# stm32f4discovery-daugherboard.net
KiCad netlist of a schematic drawn in EAGLE
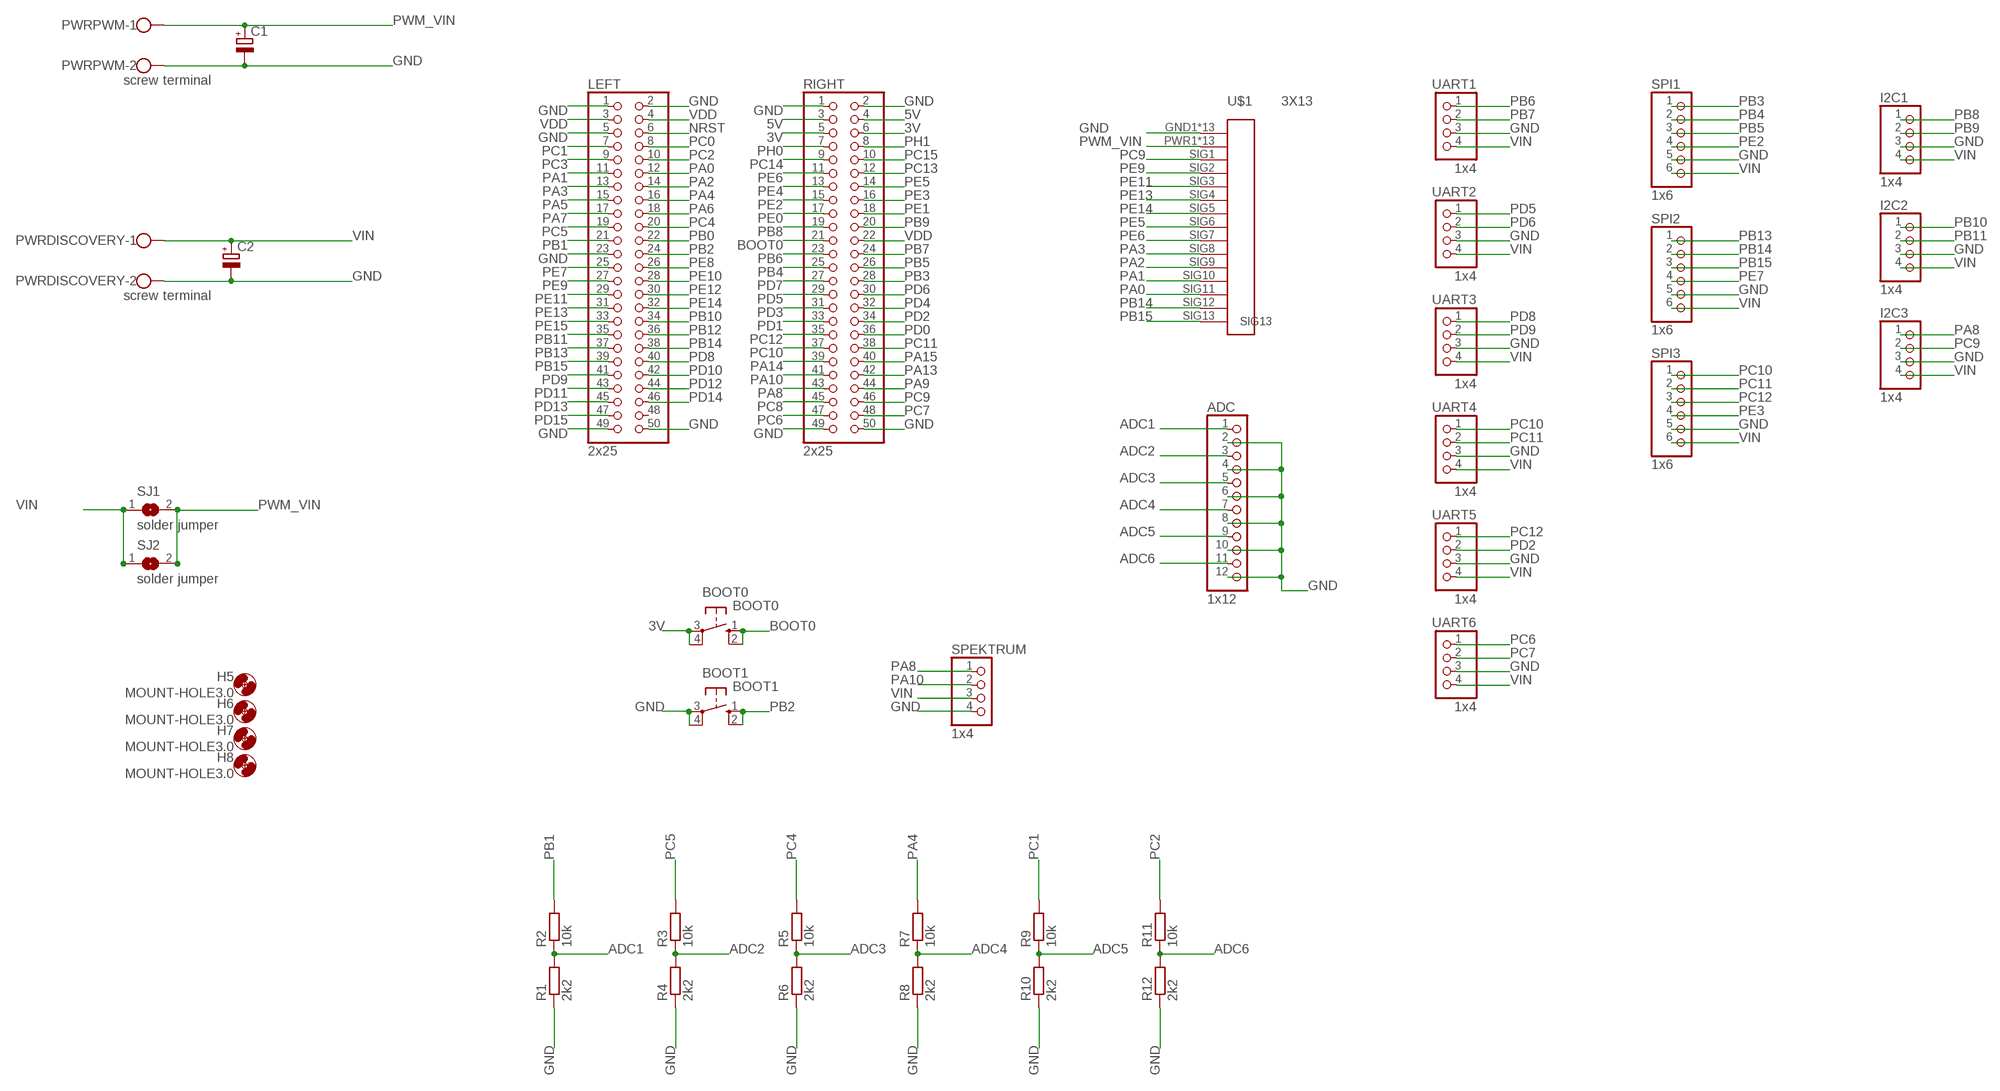
[diagram p0: schematic, sheet 1]

(export (version "E")
  (design (tool "Eeschema 10.0.6"))
  (components
    (comp (ref "ADC")
      (value "1x12")
      (footprint "eagle-import:1X12_90")
      (libsource (lib "eagle-import") (part "PINHD-1X12/90"))
    )
    (comp (ref "BOOT0")
      (value "BOOT0")
      (footprint "eagle-import:B3F-10XX")
      (fields (field (name "MPN") "B3F-1000"))
      (libsource (lib "eagle-import") (part "10-XX"))
    )
    (comp (ref "BOOT1")
      (value "BOOT1")
      (footprint "eagle-import:B3F-10XX")
      (fields (field (name "MPN") "B3F-1000"))
      (libsource (lib "eagle-import") (part "10-XX"))
    )
    (comp (ref "C1")
      (value "CPOL-EU153CLV-0807")
      (footprint "eagle-import:153CLV-0807")
      (libsource (lib "eagle-import") (part "CPOL-EU153CLV-0807"))
    )
    (comp (ref "C2")
      (value "CPOL-EU153CLV-0807")
      (footprint "eagle-import:153CLV-0807")
      (libsource (lib "eagle-import") (part "CPOL-EU153CLV-0807"))
    )
    (comp (ref "H5")
      (value "MOUNT-HOLE3.0")
      (footprint "eagle-import:3,0")
      (libsource (lib "eagle-import") (part "MOUNT-HOLE3.0"))
    )
    (comp (ref "H6")
      (value "MOUNT-HOLE3.0")
      (footprint "eagle-import:3,0")
      (libsource (lib "eagle-import") (part "MOUNT-HOLE3.0"))
    )
    (comp (ref "H7")
      (value "MOUNT-HOLE3.0")
      (footprint "eagle-import:3,0")
      (libsource (lib "eagle-import") (part "MOUNT-HOLE3.0"))
    )
    (comp (ref "H8")
      (value "MOUNT-HOLE3.0")
      (footprint "eagle-import:3,0")
      (libsource (lib "eagle-import") (part "MOUNT-HOLE3.0"))
    )
    (comp (ref "I2C1")
      (value "1x4")
      (footprint "eagle-import:1X04_90")
      (libsource (lib "eagle-import") (part "PINHD-1X4/90"))
    )
    (comp (ref "I2C2")
      (value "1x4")
      (footprint "eagle-import:1X04_90")
      (libsource (lib "eagle-import") (part "PINHD-1X4/90"))
    )
    (comp (ref "I2C3")
      (value "1x4")
      (footprint "eagle-import:1X04_90")
      (libsource (lib "eagle-import") (part "PINHD-1X4/90"))
    )
    (comp (ref "LEFT")
      (value "2x25")
      (footprint "eagle-import:2X25")
      (libsource (lib "eagle-import") (part "PINHD-2X25"))
    )
    (comp (ref "PWRDISCOVERY")
      (value "screw terminal")
      (footprint "eagle-import:W237-102")
      (fields (field (name "MPN") "237-102"))
      (libsource (lib "eagle-import") (part "W237-102"))
    )
    (comp (ref "PWRPWM")
      (value "screw terminal")
      (footprint "eagle-import:W237-102")
      (fields (field (name "MPN") "237-102"))
      (libsource (lib "eagle-import") (part "W237-102"))
    )
    (comp (ref "R1")
      (value "2k2")
      (footprint "eagle-import:M0805")
      (libsource (lib "eagle-import") (part "R-EU_M0805"))
    )
    (comp (ref "R2")
      (value "10k")
      (footprint "eagle-import:M0805")
      (libsource (lib "eagle-import") (part "R-EU_M0805"))
    )
    (comp (ref "R3")
      (value "10k")
      (footprint "eagle-import:M0805")
      (libsource (lib "eagle-import") (part "R-EU_M0805"))
    )
    (comp (ref "R4")
      (value "2k2")
      (footprint "eagle-import:M0805")
      (libsource (lib "eagle-import") (part "R-EU_M0805"))
    )
    (comp (ref "R5")
      (value "10k")
      (footprint "eagle-import:M0805")
      (libsource (lib "eagle-import") (part "R-EU_M0805"))
    )
    (comp (ref "R6")
      (value "2k2")
      (footprint "eagle-import:M0805")
      (libsource (lib "eagle-import") (part "R-EU_M0805"))
    )
    (comp (ref "R7")
      (value "10k")
      (footprint "eagle-import:M0805")
      (libsource (lib "eagle-import") (part "R-EU_M0805"))
    )
    (comp (ref "R8")
      (value "2k2")
      (footprint "eagle-import:M0805")
      (libsource (lib "eagle-import") (part "R-EU_M0805"))
    )
    (comp (ref "R9")
      (value "10k")
      (footprint "eagle-import:M0805")
      (libsource (lib "eagle-import") (part "R-EU_M0805"))
    )
    (comp (ref "R10")
      (value "2k2")
      (footprint "eagle-import:M0805")
      (libsource (lib "eagle-import") (part "R-EU_M0805"))
    )
    (comp (ref "R11")
      (value "10k")
      (footprint "eagle-import:M0805")
      (libsource (lib "eagle-import") (part "R-EU_M0805"))
    )
    (comp (ref "R12")
      (value "2k2")
      (footprint "eagle-import:M0805")
      (libsource (lib "eagle-import") (part "R-EU_M0805"))
    )
    (comp (ref "RIGHT")
      (value "2x25")
      (footprint "eagle-import:2X25")
      (libsource (lib "eagle-import") (part "PINHD-2X25"))
    )
    (comp (ref "SJ1")
      (value "solder jumper")
      (footprint "eagle-import:SJW")
      (libsource (lib "eagle-import") (part "SJW"))
    )
    (comp (ref "SJ2")
      (value "solder jumper")
      (footprint "eagle-import:SJW")
      (libsource (lib "eagle-import") (part "SJW"))
    )
    (comp (ref "SPEKTRUM")
      (value "1x4")
      (footprint "eagle-import:1X04_90")
      (libsource (lib "eagle-import") (part "PINHD-1X4/90"))
    )
    (comp (ref "SPI1")
      (value "1x6")
      (footprint "eagle-import:1X06_90")
      (libsource (lib "eagle-import") (part "PINHD-1X6/90"))
    )
    (comp (ref "SPI2")
      (value "1x6")
      (footprint "eagle-import:1X06_90")
      (libsource (lib "eagle-import") (part "PINHD-1X6/90"))
    )
    (comp (ref "SPI3")
      (value "1x6")
      (footprint "eagle-import:1X06_90")
      (libsource (lib "eagle-import") (part "PINHD-1X6/90"))
    )
    (comp (ref "U$1")
      (value "3X13")
      (footprint "eagle-import:3X13")
      (libsource (lib "eagle-import") (part "3X13"))
    )
    (comp (ref "UART1")
      (value "1x4")
      (footprint "eagle-import:1X04_90")
      (libsource (lib "eagle-import") (part "PINHD-1X4/90"))
    )
    (comp (ref "UART2")
      (value "1x4")
      (footprint "eagle-import:1X04_90")
      (libsource (lib "eagle-import") (part "PINHD-1X4/90"))
    )
    (comp (ref "UART3")
      (value "1x4")
      (footprint "eagle-import:1X04_90")
      (libsource (lib "eagle-import") (part "PINHD-1X4/90"))
    )
    (comp (ref "UART4")
      (value "1x4")
      (footprint "eagle-import:1X04_90")
      (libsource (lib "eagle-import") (part "PINHD-1X4/90"))
    )
    (comp (ref "UART5")
      (value "1x4")
      (footprint "eagle-import:1X04_90")
      (libsource (lib "eagle-import") (part "PINHD-1X4/90"))
    )
    (comp (ref "UART6")
      (value "1x4")
      (footprint "eagle-import:1X04_90")
      (libsource (lib "eagle-import") (part "PINHD-1X4/90"))
    )
  )
  (nets
    (net (code "1") (name "/3V") (class "Default")
      (node (ref "BOOT0") (pin "3") (pinfunction "P_3") (pintype "passive"))
      (node (ref "BOOT0") (pin "4") (pinfunction "P1_4") (pintype "passive"))
      (node (ref "RIGHT") (pin "5") (pinfunction "5_5") (pintype "passive"))
      (node (ref "RIGHT") (pin "6") (pinfunction "6_6") (pintype "passive"))
    )
    (net (code "2") (name "/5V") (class "Default")
      (node (ref "RIGHT") (pin "3") (pinfunction "3_3") (pintype "passive"))
      (node (ref "RIGHT") (pin "4") (pinfunction "4_4") (pintype "passive"))
    )
    (net (code "3") (name "/ADC1") (class "Default")
      (node (ref "ADC") (pin "1") (pinfunction "1_1") (pintype "passive"))
      (node (ref "R1") (pin "2") (pinfunction "2_2") (pintype "passive"))
      (node (ref "R2") (pin "1") (pinfunction "1_1") (pintype "passive"))
    )
    (net (code "4") (name "/ADC2") (class "Default")
      (node (ref "ADC") (pin "3") (pinfunction "3_3") (pintype "passive"))
      (node (ref "R3") (pin "1") (pinfunction "1_1") (pintype "passive"))
      (node (ref "R4") (pin "2") (pinfunction "2_2") (pintype "passive"))
    )
    (net (code "5") (name "/ADC3") (class "Default")
      (node (ref "ADC") (pin "5") (pinfunction "5_5") (pintype "passive"))
      (node (ref "R5") (pin "1") (pinfunction "1_1") (pintype "passive"))
      (node (ref "R6") (pin "2") (pinfunction "2_2") (pintype "passive"))
    )
    (net (code "6") (name "/ADC4") (class "Default")
      (node (ref "ADC") (pin "7") (pinfunction "7_7") (pintype "passive"))
      (node (ref "R7") (pin "1") (pinfunction "1_1") (pintype "passive"))
      (node (ref "R8") (pin "2") (pinfunction "2_2") (pintype "passive"))
    )
    (net (code "7") (name "/ADC5") (class "Default")
      (node (ref "ADC") (pin "9") (pinfunction "9_9") (pintype "passive"))
      (node (ref "R10") (pin "2") (pinfunction "2_2") (pintype "passive"))
      (node (ref "R9") (pin "1") (pinfunction "1_1") (pintype "passive"))
    )
    (net (code "8") (name "/ADC6") (class "Default")
      (node (ref "ADC") (pin "11") (pinfunction "11_11") (pintype "passive"))
      (node (ref "R11") (pin "1") (pinfunction "1_1") (pintype "passive"))
      (node (ref "R12") (pin "2") (pinfunction "2_2") (pintype "passive"))
    )
    (net (code "9") (name "/BOOT0") (class "Default")
      (node (ref "BOOT0") (pin "1") (pinfunction "S_1") (pintype "passive"))
      (node (ref "BOOT0") (pin "2") (pinfunction "S1_2") (pintype "passive"))
      (node (ref "RIGHT") (pin "21") (pinfunction "21_21") (pintype "passive"))
    )
    (net (code "10") (name "/GND") (class "Default")
      (node (ref "ADC") (pin "10") (pinfunction "10_10") (pintype "passive"))
      (node (ref "ADC") (pin "12") (pinfunction "12_12") (pintype "passive"))
      (node (ref "ADC") (pin "2") (pinfunction "2_2") (pintype "passive"))
      (node (ref "ADC") (pin "4") (pinfunction "4_4") (pintype "passive"))
      (node (ref "ADC") (pin "6") (pinfunction "6_6") (pintype "passive"))
      (node (ref "ADC") (pin "8") (pinfunction "8_8") (pintype "passive"))
      (node (ref "BOOT1") (pin "3") (pinfunction "P_3") (pintype "passive"))
      (node (ref "BOOT1") (pin "4") (pinfunction "P1_4") (pintype "passive"))
      (node (ref "C1") (pin "-") (pinfunction "-_-") (pintype "passive"))
      (node (ref "C2") (pin "-") (pinfunction "-_-") (pintype "passive"))
      (node (ref "I2C1") (pin "3") (pinfunction "3_3") (pintype "passive"))
      (node (ref "I2C2") (pin "3") (pinfunction "3_3") (pintype "passive"))
      (node (ref "I2C3") (pin "3") (pinfunction "3_3") (pintype "passive"))
      (node (ref "LEFT") (pin "1") (pinfunction "1_1") (pintype "passive"))
      (node (ref "LEFT") (pin "2") (pinfunction "2_2") (pintype "passive"))
      (node (ref "LEFT") (pin "23") (pinfunction "23_23") (pintype "passive"))
      (node (ref "LEFT") (pin "49") (pinfunction "49_49") (pintype "passive"))
      (node (ref "LEFT") (pin "5") (pinfunction "5_5") (pintype "passive"))
      (node (ref "LEFT") (pin "50") (pinfunction "50_50") (pintype "passive"))
      (node (ref "PWRDISCOVERY") (pin "2") (pinfunction "KL_2") (pintype "passive"))
      (node (ref "PWRPWM") (pin "2") (pinfunction "KL_2") (pintype "passive"))
      (node (ref "R1") (pin "1") (pinfunction "1_1") (pintype "passive"))
      (node (ref "R10") (pin "1") (pinfunction "1_1") (pintype "passive"))
      (node (ref "R12") (pin "1") (pinfunction "1_1") (pintype "passive"))
      (node (ref "R4") (pin "1") (pinfunction "1_1") (pintype "passive"))
      (node (ref "R6") (pin "1") (pinfunction "1_1") (pintype "passive"))
      (node (ref "R8") (pin "1") (pinfunction "1_1") (pintype "passive"))
      (node (ref "RIGHT") (pin "1") (pinfunction "1_1") (pintype "passive"))
      (node (ref "RIGHT") (pin "2") (pinfunction "2_2") (pintype "passive"))
      (node (ref "RIGHT") (pin "49") (pinfunction "49_49") (pintype "passive"))
      (node (ref "RIGHT") (pin "50") (pinfunction "50_50") (pintype "passive"))
      (node (ref "SPEKTRUM") (pin "4") (pinfunction "4_4") (pintype "passive"))
      (node (ref "SPI1") (pin "5") (pinfunction "5_5") (pintype "passive"))
      (node (ref "SPI2") (pin "5") (pinfunction "5_5") (pintype "passive"))
      (node (ref "SPI3") (pin "5") (pinfunction "5_5") (pintype "passive"))
      (node (ref "U$1") (pin "GND1") (pinfunction "GND_GND1") (pintype "bidirectional"))
      (node (ref "U$1") (pin "GND10") (pinfunction "GND_GND10") (pintype "bidirectional"))
      (node (ref "U$1") (pin "GND11") (pinfunction "GND_GND11") (pintype "bidirectional"))
      (node (ref "U$1") (pin "GND12") (pinfunction "GND_GND12") (pintype "bidirectional"))
      (node (ref "U$1") (pin "GND13") (pinfunction "GND_GND13") (pintype "bidirectional"))
      (node (ref "U$1") (pin "GND2") (pinfunction "GND_GND2") (pintype "bidirectional"))
      (node (ref "U$1") (pin "GND3") (pinfunction "GND_GND3") (pintype "bidirectional"))
      (node (ref "U$1") (pin "GND4") (pinfunction "GND_GND4") (pintype "bidirectional"))
      (node (ref "U$1") (pin "GND5") (pinfunction "GND_GND5") (pintype "bidirectional"))
      (node (ref "U$1") (pin "GND6") (pinfunction "GND_GND6") (pintype "bidirectional"))
      (node (ref "U$1") (pin "GND7") (pinfunction "GND_GND7") (pintype "bidirectional"))
      (node (ref "U$1") (pin "GND8") (pinfunction "GND_GND8") (pintype "bidirectional"))
      (node (ref "U$1") (pin "GND9") (pinfunction "GND_GND9") (pintype "bidirectional"))
      (node (ref "UART1") (pin "3") (pinfunction "3_3") (pintype "passive"))
      (node (ref "UART2") (pin "3") (pinfunction "3_3") (pintype "passive"))
      (node (ref "UART3") (pin "3") (pinfunction "3_3") (pintype "passive"))
      (node (ref "UART4") (pin "3") (pinfunction "3_3") (pintype "passive"))
      (node (ref "UART5") (pin "3") (pinfunction "3_3") (pintype "passive"))
      (node (ref "UART6") (pin "3") (pinfunction "3_3") (pintype "passive"))
    )
    (net (code "11") (name "/NRST") (class "Default")
      (node (ref "LEFT") (pin "6") (pinfunction "6_6") (pintype "passive"))
    )
    (net (code "12") (name "/PA0") (class "Default")
      (node (ref "LEFT") (pin "12") (pinfunction "12_12") (pintype "passive"))
      (node (ref "U$1") (pin "SIG11") (pinfunction "SIG11_SIG11") (pintype "bidirectional"))
    )
    (net (code "13") (name "/PA1") (class "Default")
      (node (ref "LEFT") (pin "11") (pinfunction "11_11") (pintype "passive"))
      (node (ref "U$1") (pin "SIG10") (pinfunction "SIG10_SIG10") (pintype "bidirectional"))
    )
    (net (code "14") (name "/PA2") (class "Default")
      (node (ref "LEFT") (pin "14") (pinfunction "14_14") (pintype "passive"))
      (node (ref "U$1") (pin "SIG9") (pinfunction "SIG9_SIG9") (pintype "bidirectional"))
    )
    (net (code "15") (name "/PA3") (class "Default")
      (node (ref "LEFT") (pin "13") (pinfunction "13_13") (pintype "passive"))
      (node (ref "U$1") (pin "SIG8") (pinfunction "SIG8_SIG8") (pintype "bidirectional"))
    )
    (net (code "16") (name "/PA4") (class "Default")
      (node (ref "LEFT") (pin "16") (pinfunction "16_16") (pintype "passive"))
      (node (ref "R7") (pin "2") (pinfunction "2_2") (pintype "passive"))
    )
    (net (code "17") (name "/PA5") (class "Default")
      (node (ref "LEFT") (pin "15") (pinfunction "15_15") (pintype "passive"))
    )
    (net (code "18") (name "/PA6") (class "Default")
      (node (ref "LEFT") (pin "18") (pinfunction "18_18") (pintype "passive"))
    )
    (net (code "19") (name "/PA7") (class "Default")
      (node (ref "LEFT") (pin "17") (pinfunction "17_17") (pintype "passive"))
    )
    (net (code "20") (name "/PA8") (class "Default")
      (node (ref "I2C3") (pin "1") (pinfunction "1_1") (pintype "passive"))
      (node (ref "RIGHT") (pin "43") (pinfunction "43_43") (pintype "passive"))
      (node (ref "SPEKTRUM") (pin "1") (pinfunction "1_1") (pintype "passive"))
    )
    (net (code "21") (name "/PA9") (class "Default")
      (node (ref "RIGHT") (pin "44") (pinfunction "44_44") (pintype "passive"))
    )
    (net (code "22") (name "/PA10") (class "Default")
      (node (ref "RIGHT") (pin "41") (pinfunction "41_41") (pintype "passive"))
      (node (ref "SPEKTRUM") (pin "2") (pinfunction "2_2") (pintype "passive"))
    )
    (net (code "23") (name "/PA13") (class "Default")
      (node (ref "RIGHT") (pin "42") (pinfunction "42_42") (pintype "passive"))
    )
    (net (code "24") (name "/PA14") (class "Default")
      (node (ref "RIGHT") (pin "39") (pinfunction "39_39") (pintype "passive"))
    )
    (net (code "25") (name "/PA15") (class "Default")
      (node (ref "RIGHT") (pin "40") (pinfunction "40_40") (pintype "passive"))
    )
    (net (code "26") (name "/PB0") (class "Default")
      (node (ref "LEFT") (pin "22") (pinfunction "22_22") (pintype "passive"))
    )
    (net (code "27") (name "/PB1") (class "Default")
      (node (ref "LEFT") (pin "21") (pinfunction "21_21") (pintype "passive"))
      (node (ref "R2") (pin "2") (pinfunction "2_2") (pintype "passive"))
    )
    (net (code "28") (name "/PB2") (class "Default")
      (node (ref "BOOT1") (pin "1") (pinfunction "S_1") (pintype "passive"))
      (node (ref "BOOT1") (pin "2") (pinfunction "S1_2") (pintype "passive"))
      (node (ref "LEFT") (pin "24") (pinfunction "24_24") (pintype "passive"))
    )
    (net (code "29") (name "/PB3") (class "Default")
      (node (ref "RIGHT") (pin "28") (pinfunction "28_28") (pintype "passive"))
      (node (ref "SPI1") (pin "1") (pinfunction "1_1") (pintype "passive"))
    )
    (net (code "30") (name "/PB4") (class "Default")
      (node (ref "RIGHT") (pin "25") (pinfunction "25_25") (pintype "passive"))
      (node (ref "SPI1") (pin "2") (pinfunction "2_2") (pintype "passive"))
    )
    (net (code "31") (name "/PB5") (class "Default")
      (node (ref "RIGHT") (pin "26") (pinfunction "26_26") (pintype "passive"))
      (node (ref "SPI1") (pin "3") (pinfunction "3_3") (pintype "passive"))
    )
    (net (code "32") (name "/PB6") (class "Default")
      (node (ref "RIGHT") (pin "23") (pinfunction "23_23") (pintype "passive"))
      (node (ref "UART1") (pin "1") (pinfunction "1_1") (pintype "passive"))
    )
    (net (code "33") (name "/PB7") (class "Default")
      (node (ref "RIGHT") (pin "24") (pinfunction "24_24") (pintype "passive"))
      (node (ref "UART1") (pin "2") (pinfunction "2_2") (pintype "passive"))
    )
    (net (code "34") (name "/PB8") (class "Default")
      (node (ref "I2C1") (pin "1") (pinfunction "1_1") (pintype "passive"))
      (node (ref "RIGHT") (pin "19") (pinfunction "19_19") (pintype "passive"))
    )
    (net (code "35") (name "/PB9") (class "Default")
      (node (ref "I2C1") (pin "2") (pinfunction "2_2") (pintype "passive"))
      (node (ref "RIGHT") (pin "20") (pinfunction "20_20") (pintype "passive"))
    )
    (net (code "36") (name "/PB10") (class "Default")
      (node (ref "I2C2") (pin "1") (pinfunction "1_1") (pintype "passive"))
      (node (ref "LEFT") (pin "34") (pinfunction "34_34") (pintype "passive"))
    )
    (net (code "37") (name "/PB11") (class "Default")
      (node (ref "I2C2") (pin "2") (pinfunction "2_2") (pintype "passive"))
      (node (ref "LEFT") (pin "35") (pinfunction "35_35") (pintype "passive"))
    )
    (net (code "38") (name "/PB12") (class "Default")
      (node (ref "LEFT") (pin "36") (pinfunction "36_36") (pintype "passive"))
    )
    (net (code "39") (name "/PB13") (class "Default")
      (node (ref "LEFT") (pin "37") (pinfunction "37_37") (pintype "passive"))
      (node (ref "SPI2") (pin "1") (pinfunction "1_1") (pintype "passive"))
    )
    (net (code "40") (name "/PB14") (class "Default")
      (node (ref "LEFT") (pin "38") (pinfunction "38_38") (pintype "passive"))
      (node (ref "SPI2") (pin "2") (pinfunction "2_2") (pintype "passive"))
      (node (ref "U$1") (pin "SIG12") (pinfunction "SIG12_SIG12") (pintype "bidirectional"))
    )
    (net (code "41") (name "/PB15") (class "Default")
      (node (ref "LEFT") (pin "39") (pinfunction "39_39") (pintype "passive"))
      (node (ref "SPI2") (pin "3") (pinfunction "3_3") (pintype "passive"))
      (node (ref "U$1") (pin "SIG13") (pinfunction "SIG13_SIG13") (pintype "bidirectional"))
    )
    (net (code "42") (name "/PC0") (class "Default")
      (node (ref "LEFT") (pin "8") (pinfunction "8_8") (pintype "passive"))
    )
    (net (code "43") (name "/PC1") (class "Default")
      (node (ref "LEFT") (pin "7") (pinfunction "7_7") (pintype "passive"))
      (node (ref "R9") (pin "2") (pinfunction "2_2") (pintype "passive"))
    )
    (net (code "44") (name "/PC2") (class "Default")
      (node (ref "LEFT") (pin "10") (pinfunction "10_10") (pintype "passive"))
      (node (ref "R11") (pin "2") (pinfunction "2_2") (pintype "passive"))
    )
    (net (code "45") (name "/PC3") (class "Default")
      (node (ref "LEFT") (pin "9") (pinfunction "9_9") (pintype "passive"))
    )
    (net (code "46") (name "/PC4") (class "Default")
      (node (ref "LEFT") (pin "20") (pinfunction "20_20") (pintype "passive"))
      (node (ref "R5") (pin "2") (pinfunction "2_2") (pintype "passive"))
    )
    (net (code "47") (name "/PC5") (class "Default")
      (node (ref "LEFT") (pin "19") (pinfunction "19_19") (pintype "passive"))
      (node (ref "R3") (pin "2") (pinfunction "2_2") (pintype "passive"))
    )
    (net (code "48") (name "/PC6") (class "Default")
      (node (ref "RIGHT") (pin "47") (pinfunction "47_47") (pintype "passive"))
      (node (ref "UART6") (pin "1") (pinfunction "1_1") (pintype "passive"))
    )
    (net (code "49") (name "/PC7") (class "Default")
      (node (ref "RIGHT") (pin "48") (pinfunction "48_48") (pintype "passive"))
      (node (ref "UART6") (pin "2") (pinfunction "2_2") (pintype "passive"))
    )
    (net (code "50") (name "/PC8") (class "Default")
      (node (ref "RIGHT") (pin "45") (pinfunction "45_45") (pintype "passive"))
    )
    (net (code "51") (name "/PC9") (class "Default")
      (node (ref "I2C3") (pin "2") (pinfunction "2_2") (pintype "passive"))
      (node (ref "RIGHT") (pin "46") (pinfunction "46_46") (pintype "passive"))
      (node (ref "U$1") (pin "SIG1") (pinfunction "SIG1_SIG1") (pintype "bidirectional"))
    )
    (net (code "52") (name "/PC10") (class "Default")
      (node (ref "RIGHT") (pin "37") (pinfunction "37_37") (pintype "passive"))
      (node (ref "SPI3") (pin "1") (pinfunction "1_1") (pintype "passive"))
      (node (ref "UART4") (pin "1") (pinfunction "1_1") (pintype "passive"))
    )
    (net (code "53") (name "/PC11") (class "Default")
      (node (ref "RIGHT") (pin "38") (pinfunction "38_38") (pintype "passive"))
      (node (ref "SPI3") (pin "2") (pinfunction "2_2") (pintype "passive"))
      (node (ref "UART4") (pin "2") (pinfunction "2_2") (pintype "passive"))
    )
    (net (code "54") (name "/PC12") (class "Default")
      (node (ref "RIGHT") (pin "35") (pinfunction "35_35") (pintype "passive"))
      (node (ref "SPI3") (pin "3") (pinfunction "3_3") (pintype "passive"))
      (node (ref "UART5") (pin "1") (pinfunction "1_1") (pintype "passive"))
    )
    (net (code "55") (name "/PC13") (class "Default")
      (node (ref "RIGHT") (pin "12") (pinfunction "12_12") (pintype "passive"))
    )
    (net (code "56") (name "/PC14") (class "Default")
      (node (ref "RIGHT") (pin "9") (pinfunction "9_9") (pintype "passive"))
    )
    (net (code "57") (name "/PC15") (class "Default")
      (node (ref "RIGHT") (pin "10") (pinfunction "10_10") (pintype "passive"))
    )
    (net (code "58") (name "/PD0") (class "Default")
      (node (ref "RIGHT") (pin "36") (pinfunction "36_36") (pintype "passive"))
    )
    (net (code "59") (name "/PD1") (class "Default")
      (node (ref "RIGHT") (pin "33") (pinfunction "33_33") (pintype "passive"))
    )
    (net (code "60") (name "/PD2") (class "Default")
      (node (ref "RIGHT") (pin "34") (pinfunction "34_34") (pintype "passive"))
      (node (ref "UART5") (pin "2") (pinfunction "2_2") (pintype "passive"))
    )
    (net (code "61") (name "/PD3") (class "Default")
      (node (ref "RIGHT") (pin "31") (pinfunction "31_31") (pintype "passive"))
    )
    (net (code "62") (name "/PD4") (class "Default")
      (node (ref "RIGHT") (pin "32") (pinfunction "32_32") (pintype "passive"))
    )
    (net (code "63") (name "/PD5") (class "Default")
      (node (ref "RIGHT") (pin "29") (pinfunction "29_29") (pintype "passive"))
      (node (ref "UART2") (pin "1") (pinfunction "1_1") (pintype "passive"))
    )
    (net (code "64") (name "/PD6") (class "Default")
      (node (ref "RIGHT") (pin "30") (pinfunction "30_30") (pintype "passive"))
      (node (ref "UART2") (pin "2") (pinfunction "2_2") (pintype "passive"))
    )
    (net (code "65") (name "/PD7") (class "Default")
      (node (ref "RIGHT") (pin "27") (pinfunction "27_27") (pintype "passive"))
    )
    (net (code "66") (name "/PD8") (class "Default")
      (node (ref "LEFT") (pin "40") (pinfunction "40_40") (pintype "passive"))
      (node (ref "UART3") (pin "1") (pinfunction "1_1") (pintype "passive"))
    )
    (net (code "67") (name "/PD9") (class "Default")
      (node (ref "LEFT") (pin "41") (pinfunction "41_41") (pintype "passive"))
      (node (ref "UART3") (pin "2") (pinfunction "2_2") (pintype "passive"))
    )
    (net (code "68") (name "/PD10") (class "Default")
      (node (ref "LEFT") (pin "42") (pinfunction "42_42") (pintype "passive"))
    )
    (net (code "69") (name "/PD11") (class "Default")
      (node (ref "LEFT") (pin "43") (pinfunction "43_43") (pintype "passive"))
    )
    (net (code "70") (name "/PD12") (class "Default")
      (node (ref "LEFT") (pin "44") (pinfunction "44_44") (pintype "passive"))
    )
    (net (code "71") (name "/PD13") (class "Default")
      (node (ref "LEFT") (pin "45") (pinfunction "45_45") (pintype "passive"))
    )
    (net (code "72") (name "/PD14") (class "Default")
      (node (ref "LEFT") (pin "46") (pinfunction "46_46") (pintype "passive"))
    )
    (net (code "73") (name "/PD15") (class "Default")
      (node (ref "LEFT") (pin "47") (pinfunction "47_47") (pintype "passive"))
    )
    (net (code "74") (name "/PE0") (class "Default")
      (node (ref "RIGHT") (pin "17") (pinfunction "17_17") (pintype "passive"))
    )
    (net (code "75") (name "/PE1") (class "Default")
      (node (ref "RIGHT") (pin "18") (pinfunction "18_18") (pintype "passive"))
    )
    (net (code "76") (name "/PE2") (class "Default")
      (node (ref "RIGHT") (pin "15") (pinfunction "15_15") (pintype "passive"))
      (node (ref "SPI1") (pin "4") (pinfunction "4_4") (pintype "passive"))
    )
    (net (code "77") (name "/PE3") (class "Default")
      (node (ref "RIGHT") (pin "16") (pinfunction "16_16") (pintype "passive"))
      (node (ref "SPI3") (pin "4") (pinfunction "4_4") (pintype "passive"))
    )
    (net (code "78") (name "/PE4") (class "Default")
      (node (ref "RIGHT") (pin "13") (pinfunction "13_13") (pintype "passive"))
    )
    (net (code "79") (name "/PE5") (class "Default")
      (node (ref "RIGHT") (pin "14") (pinfunction "14_14") (pintype "passive"))
      (node (ref "U$1") (pin "SIG6") (pinfunction "SIG6_SIG6") (pintype "bidirectional"))
    )
    (net (code "80") (name "/PE6") (class "Default")
      (node (ref "RIGHT") (pin "11") (pinfunction "11_11") (pintype "passive"))
      (node (ref "U$1") (pin "SIG7") (pinfunction "SIG7_SIG7") (pintype "bidirectional"))
    )
    (net (code "81") (name "/PE7") (class "Default")
      (node (ref "LEFT") (pin "25") (pinfunction "25_25") (pintype "passive"))
      (node (ref "SPI2") (pin "4") (pinfunction "4_4") (pintype "passive"))
    )
    (net (code "82") (name "/PE8") (class "Default")
      (node (ref "LEFT") (pin "26") (pinfunction "26_26") (pintype "passive"))
    )
    (net (code "83") (name "/PE9") (class "Default")
      (node (ref "LEFT") (pin "27") (pinfunction "27_27") (pintype "passive"))
      (node (ref "U$1") (pin "SIG2") (pinfunction "SIG2_SIG2") (pintype "bidirectional"))
    )
    (net (code "84") (name "/PE10") (class "Default")
      (node (ref "LEFT") (pin "28") (pinfunction "28_28") (pintype "passive"))
    )
    (net (code "85") (name "/PE11") (class "Default")
      (node (ref "LEFT") (pin "29") (pinfunction "29_29") (pintype "passive"))
      (node (ref "U$1") (pin "SIG3") (pinfunction "SIG3_SIG3") (pintype "bidirectional"))
    )
    (net (code "86") (name "/PE12") (class "Default")
      (node (ref "LEFT") (pin "30") (pinfunction "30_30") (pintype "passive"))
    )
    (net (code "87") (name "/PE13") (class "Default")
      (node (ref "LEFT") (pin "31") (pinfunction "31_31") (pintype "passive"))
      (node (ref "U$1") (pin "SIG4") (pinfunction "SIG4_SIG4") (pintype "bidirectional"))
    )
    (net (code "88") (name "/PE14") (class "Default")
      (node (ref "LEFT") (pin "32") (pinfunction "32_32") (pintype "passive"))
      (node (ref "U$1") (pin "SIG5") (pinfunction "SIG5_SIG5") (pintype "bidirectional"))
    )
    (net (code "89") (name "/PE15") (class "Default")
      (node (ref "LEFT") (pin "33") (pinfunction "33_33") (pintype "passive"))
    )
    (net (code "90") (name "/PH0") (class "Default")
      (node (ref "RIGHT") (pin "7") (pinfunction "7_7") (pintype "passive"))
    )
    (net (code "91") (name "/PH1") (class "Default")
      (node (ref "RIGHT") (pin "8") (pinfunction "8_8") (pintype "passive"))
    )
    (net (code "92") (name "/PWM_VIN") (class "Default")
      (node (ref "C1") (pin "+") (pinfunction "+_+") (pintype "passive"))
      (node (ref "PWRPWM") (pin "1") (pinfunction "KL_1") (pintype "passive"))
      (node (ref "SJ1") (pin "2") (pinfunction "2_2") (pintype "passive"))
      (node (ref "SJ2") (pin "2") (pinfunction "2_2") (pintype "passive"))
      (node (ref "U$1") (pin "PWR1") (pinfunction "PWR_PWR1") (pintype "bidirectional"))
      (node (ref "U$1") (pin "PWR10") (pinfunction "PWR_PWR10") (pintype "bidirectional"))
      (node (ref "U$1") (pin "PWR11") (pinfunction "PWR_PWR11") (pintype "bidirectional"))
      (node (ref "U$1") (pin "PWR12") (pinfunction "PWR_PWR12") (pintype "bidirectional"))
      (node (ref "U$1") (pin "PWR13") (pinfunction "PWR_PWR13") (pintype "bidirectional"))
      (node (ref "U$1") (pin "PWR2") (pinfunction "PWR_PWR2") (pintype "bidirectional"))
      (node (ref "U$1") (pin "PWR3") (pinfunction "PWR_PWR3") (pintype "bidirectional"))
      (node (ref "U$1") (pin "PWR4") (pinfunction "PWR_PWR4") (pintype "bidirectional"))
      (node (ref "U$1") (pin "PWR5") (pinfunction "PWR_PWR5") (pintype "bidirectional"))
      (node (ref "U$1") (pin "PWR6") (pinfunction "PWR_PWR6") (pintype "bidirectional"))
      (node (ref "U$1") (pin "PWR7") (pinfunction "PWR_PWR7") (pintype "bidirectional"))
      (node (ref "U$1") (pin "PWR8") (pinfunction "PWR_PWR8") (pintype "bidirectional"))
      (node (ref "U$1") (pin "PWR9") (pinfunction "PWR_PWR9") (pintype "bidirectional"))
    )
    (net (code "93") (name "/VDD") (class "Default")
      (node (ref "LEFT") (pin "3") (pinfunction "3_3") (pintype "passive"))
      (node (ref "LEFT") (pin "4") (pinfunction "4_4") (pintype "passive"))
      (node (ref "RIGHT") (pin "22") (pinfunction "22_22") (pintype "passive"))
    )
    (net (code "94") (name "/VIN") (class "Default")
      (node (ref "C2") (pin "+") (pinfunction "+_+") (pintype "passive"))
      (node (ref "I2C1") (pin "4") (pinfunction "4_4") (pintype "passive"))
      (node (ref "I2C2") (pin "4") (pinfunction "4_4") (pintype "passive"))
      (node (ref "I2C3") (pin "4") (pinfunction "4_4") (pintype "passive"))
      (node (ref "PWRDISCOVERY") (pin "1") (pinfunction "KL_1") (pintype "passive"))
      (node (ref "SJ1") (pin "1") (pinfunction "1_1") (pintype "passive"))
      (node (ref "SJ2") (pin "1") (pinfunction "1_1") (pintype "passive"))
      (node (ref "SPEKTRUM") (pin "3") (pinfunction "3_3") (pintype "passive"))
      (node (ref "SPI1") (pin "6") (pinfunction "6_6") (pintype "passive"))
      (node (ref "SPI2") (pin "6") (pinfunction "6_6") (pintype "passive"))
      (node (ref "SPI3") (pin "6") (pinfunction "6_6") (pintype "passive"))
      (node (ref "UART1") (pin "4") (pinfunction "4_4") (pintype "passive"))
      (node (ref "UART2") (pin "4") (pinfunction "4_4") (pintype "passive"))
      (node (ref "UART3") (pin "4") (pinfunction "4_4") (pintype "passive"))
      (node (ref "UART4") (pin "4") (pinfunction "4_4") (pintype "passive"))
      (node (ref "UART5") (pin "4") (pinfunction "4_4") (pintype "passive"))
      (node (ref "UART6") (pin "4") (pinfunction "4_4") (pintype "passive"))
    )
    (net (code "95") (name "unconnected-(LEFT-Pad48)") (class "Default")
      (node (ref "LEFT") (pin "48") (pinfunction "48_48") (pintype "passive"))
    )
  )
)
